# demo.net
KiCad netlist of a schematic drawn in EAGLE
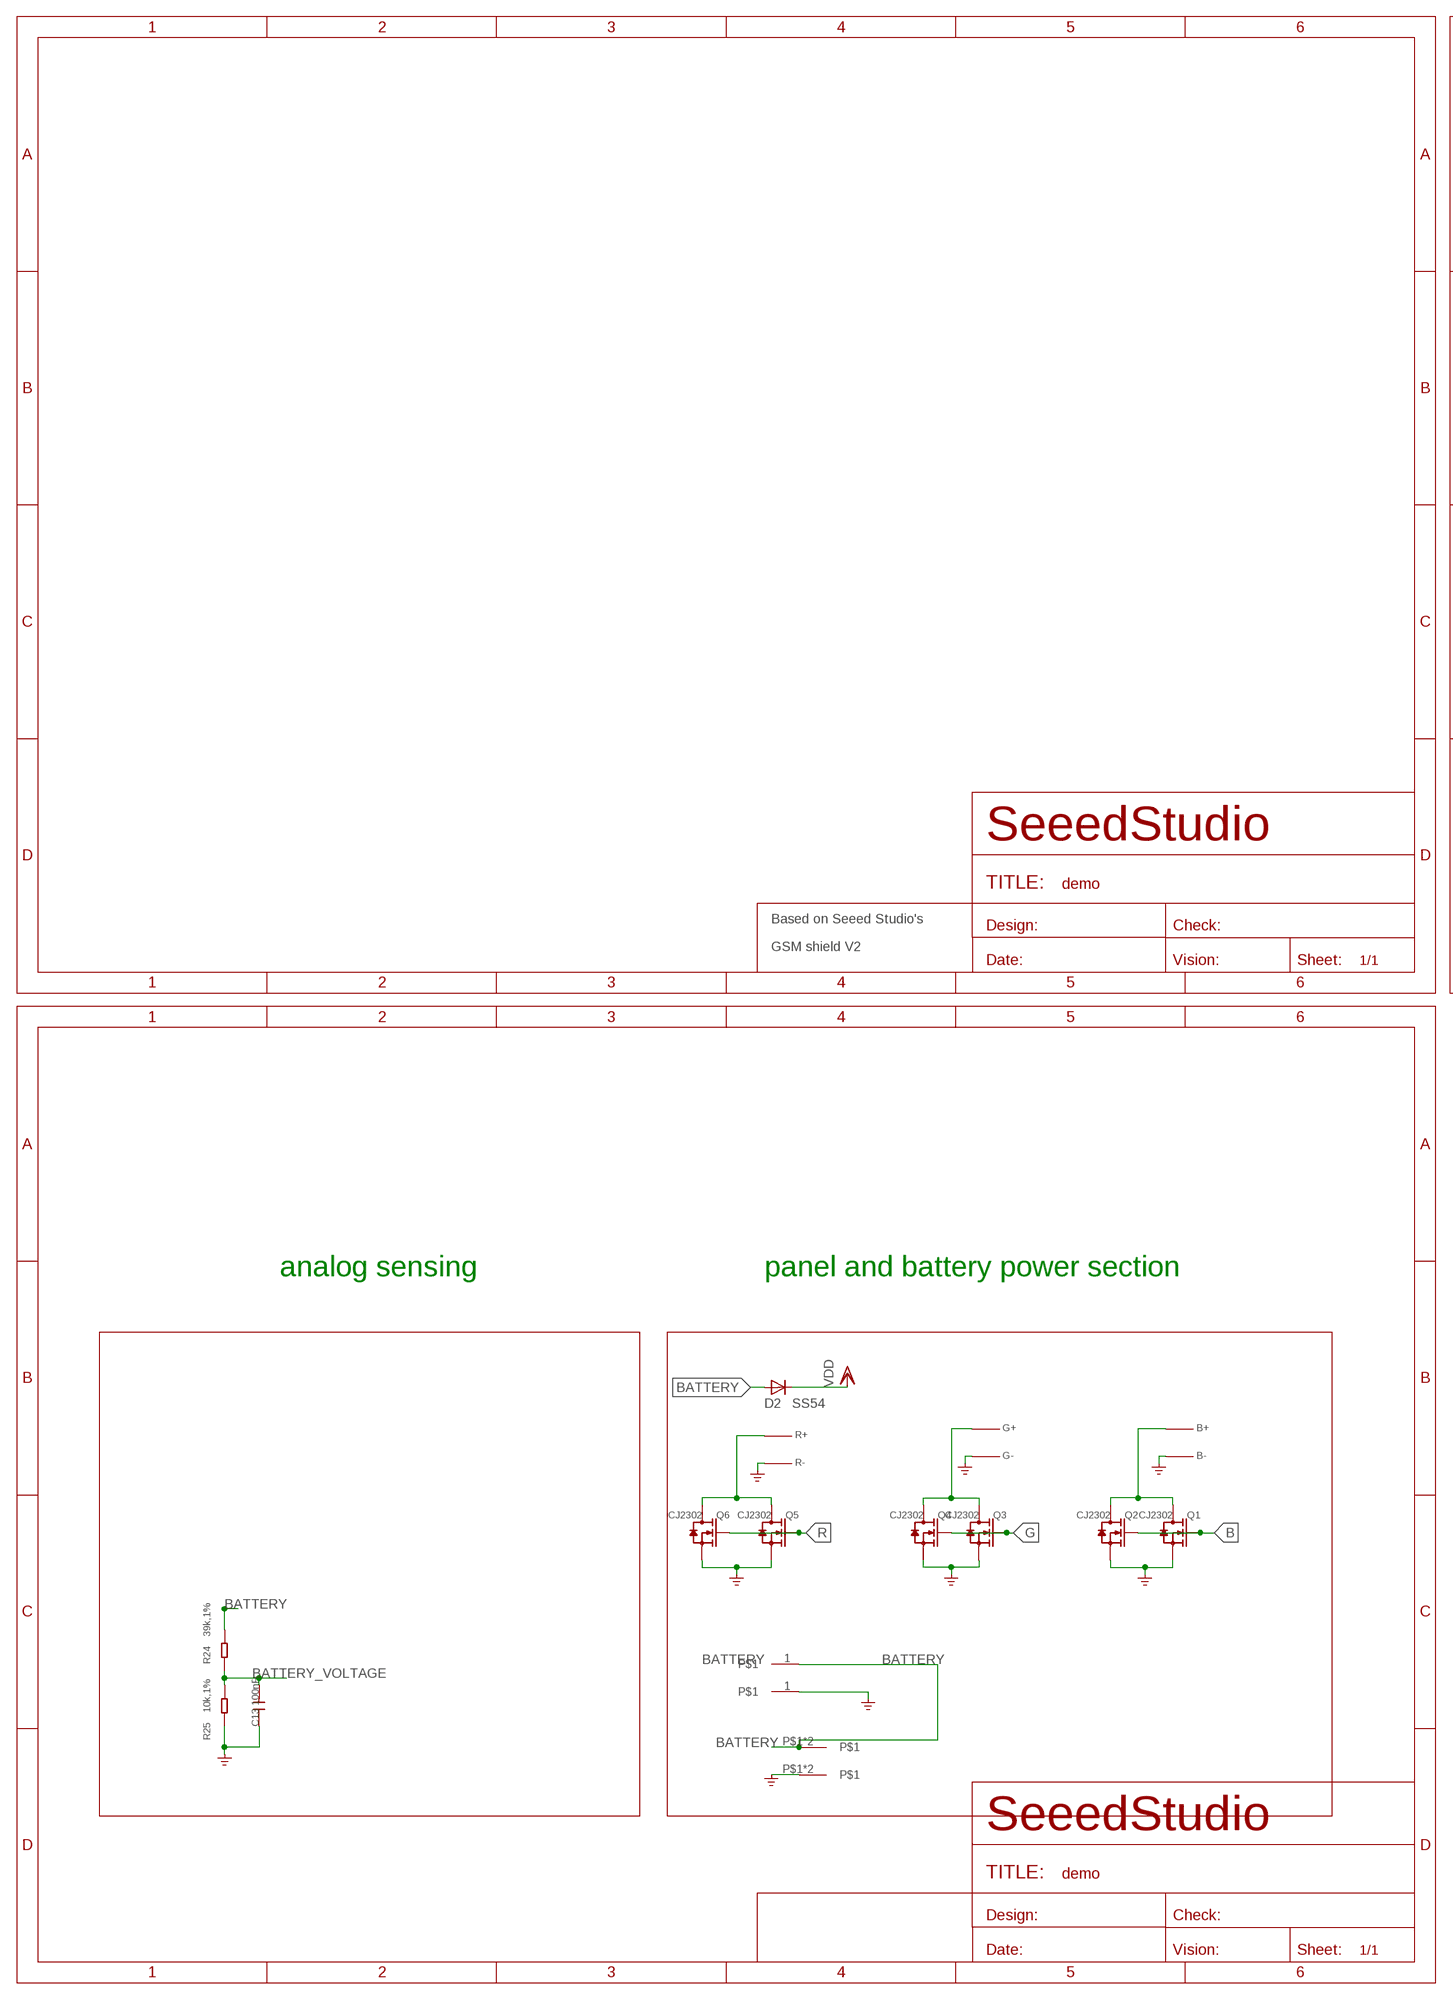
[diagram p0: schematic, sheet 1, part 1 of 2]
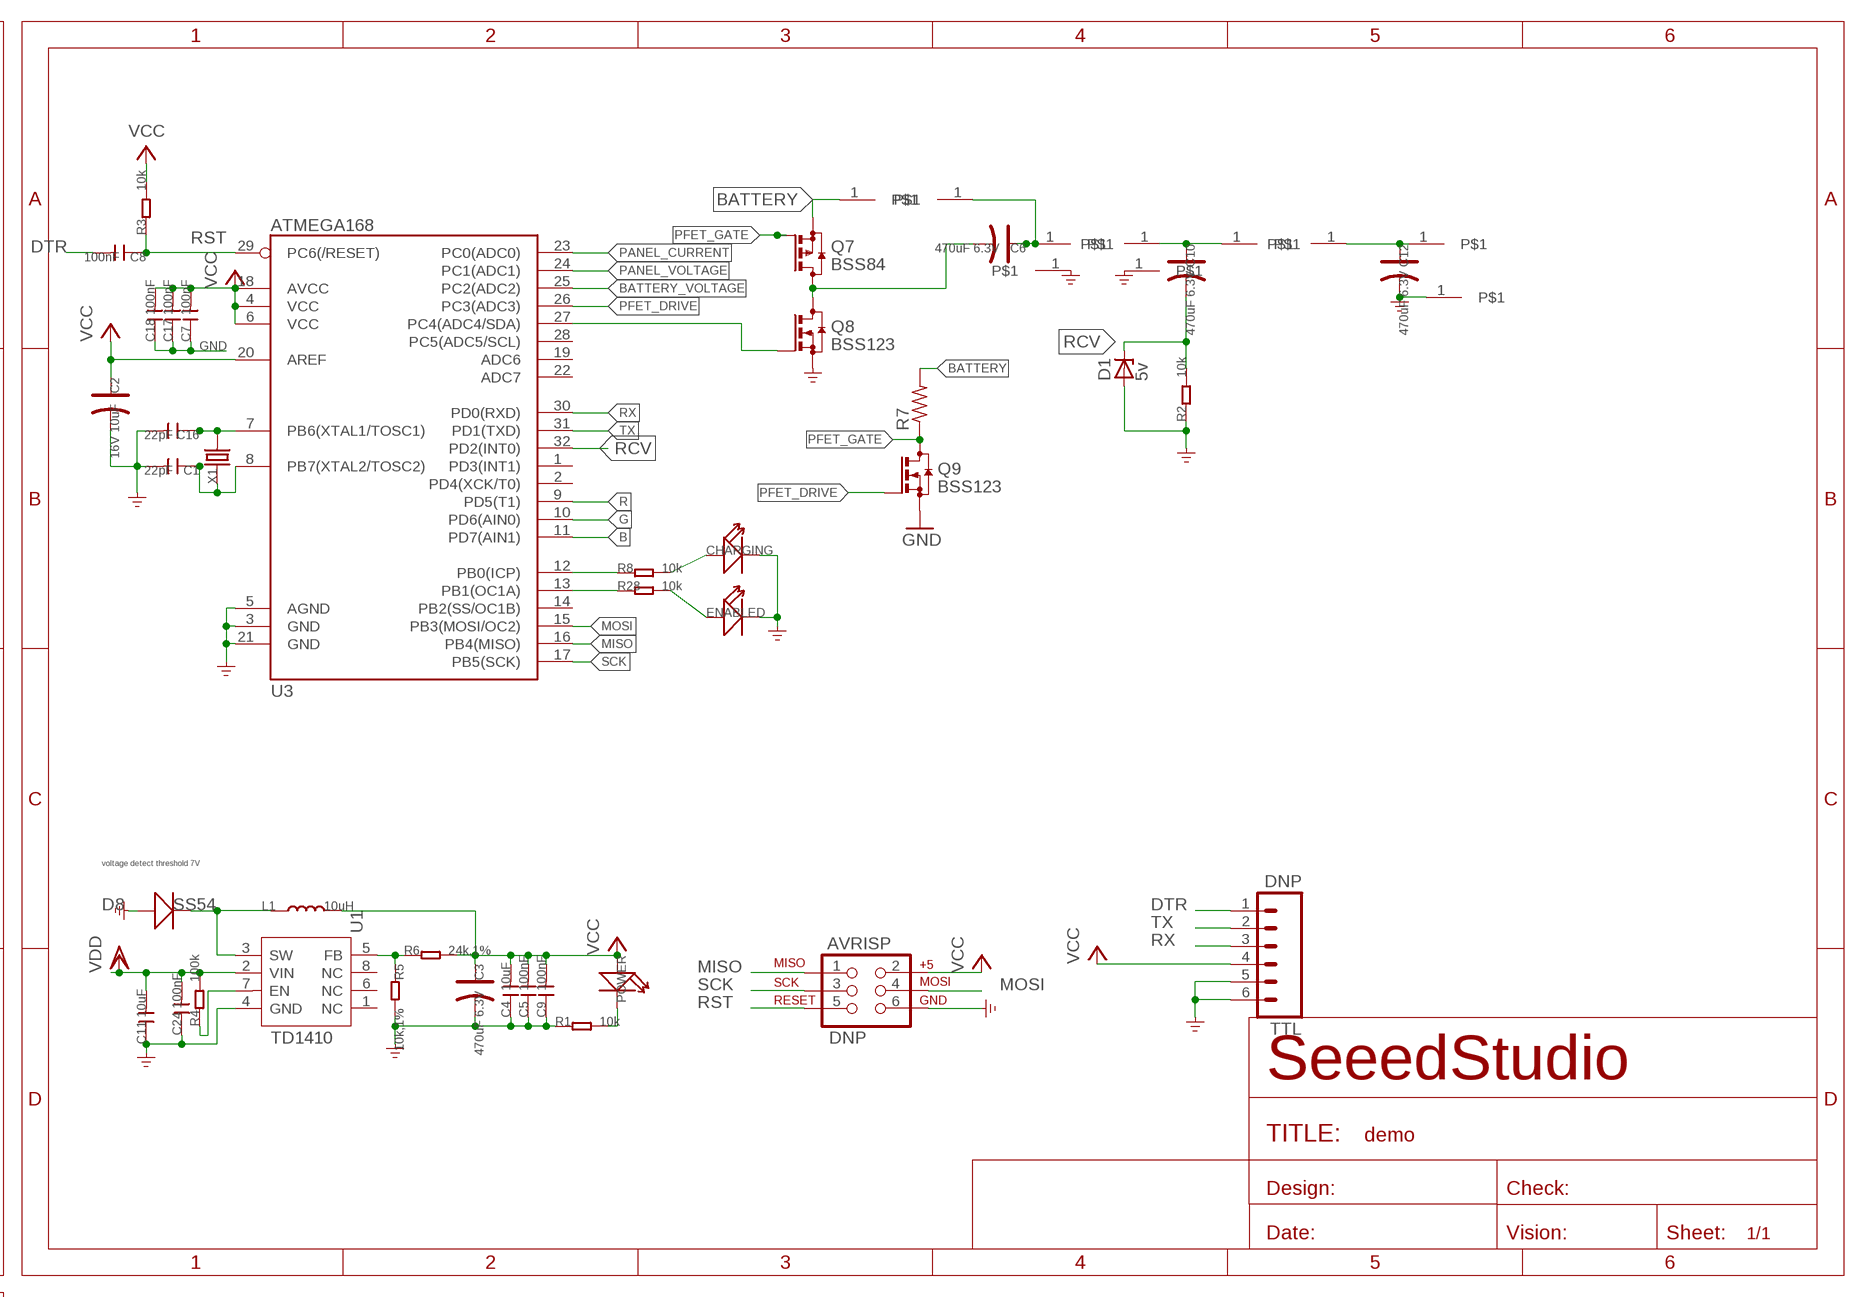
[diagram p1: schematic, sheet 1, part 2 of 2]

(export (version "E")
  (design (tool "Eeschema 10.0.6"))
  (components
    (comp (ref "AVRISP")
      (value "DNP")
      (footprint "eagle-import:2X3_LOCK")
      (libsource (lib "eagle-import") (part "AVR_SPI_PRG_62X3_LOCK"))
    )
    (comp (ref "B+")
      (value "TINYPIPES_BATTSBATT")
      (footprint "eagle-import:TINYPIPES_SBATT")
      (libsource (lib "eagle-import") (part "TINYPIPES_BATTSBATT"))
    )
    (comp (ref "B-")
      (value "TINYPIPES_BATTSBATT")
      (footprint "eagle-import:TINYPIPES_SBATT")
      (libsource (lib "eagle-import") (part "TINYPIPES_BATTSBATT"))
    )
    (comp (ref "BATTERY+")
      (value "TINYPIPES_BATTBATT")
      (footprint "eagle-import:TINYPIPES_BATT")
      (libsource (lib "eagle-import") (part "tinyPipes_v2.5_TINYPIPES_BATTBATT"))
    )
    (comp (ref "BATTERY-")
      (value "TINYPIPES_BATTBATT")
      (footprint "eagle-import:TINYPIPES_BATT")
      (libsource (lib "eagle-import") (part "tinyPipes_v2.5_TINYPIPES_BATTBATT"))
    )
    (comp (ref "C1")
      (value "22pF")
      (footprint "eagle-import:C0603")
      (libsource (lib "eagle-import") (part "C-0603"))
    )
    (comp (ref "C2")
      (value "16V 10uF")
      (footprint "eagle-import:AVX-A")
      (libsource (lib "eagle-import") (part "CAP-AVX-A"))
    )
    (comp (ref "C3")
      (value "470uF 6.3V")
      (footprint "eagle-import:AVX-D")
      (libsource (lib "eagle-import") (part "CAP-AVX-D"))
    )
    (comp (ref "C4")
      (value "10uF")
      (footprint "eagle-import:C0805")
      (libsource (lib "eagle-import") (part "C-0805"))
    )
    (comp (ref "C5")
      (value "100nF")
      (footprint "eagle-import:C0603")
      (libsource (lib "eagle-import") (part "C-0603"))
    )
    (comp (ref "C6")
      (value "470uF 6.3V")
      (footprint "eagle-import:AVX-D")
      (libsource (lib "eagle-import") (part "CAP-AVX-D"))
    )
    (comp (ref "C7")
      (value "100nF")
      (footprint "eagle-import:C0603")
      (libsource (lib "eagle-import") (part "C-0603"))
    )
    (comp (ref "C8")
      (value "100nF")
      (footprint "eagle-import:C0603")
      (libsource (lib "eagle-import") (part "C-0603"))
    )
    (comp (ref "C9")
      (value "100nF")
      (footprint "eagle-import:C0603")
      (libsource (lib "eagle-import") (part "C-0603"))
    )
    (comp (ref "C10")
      (value "470uF 6.3V")
      (footprint "eagle-import:AVX-D")
      (libsource (lib "eagle-import") (part "CAP-AVX-D"))
    )
    (comp (ref "C11")
      (value "10uF")
      (footprint "eagle-import:C0805")
      (libsource (lib "eagle-import") (part "C-0805"))
    )
    (comp (ref "C12")
      (value "470uF 6.3V")
      (footprint "eagle-import:AVX-D")
      (libsource (lib "eagle-import") (part "CAP-AVX-D"))
    )
    (comp (ref "C13")
      (value "100nF")
      (footprint "eagle-import:C0603")
      (libsource (lib "eagle-import") (part "C-0603"))
    )
    (comp (ref "C16")
      (value "22pF")
      (footprint "eagle-import:C0603")
      (libsource (lib "eagle-import") (part "C-0603"))
    )
    (comp (ref "C17")
      (value "100nF")
      (footprint "eagle-import:C0603")
      (libsource (lib "eagle-import") (part "C-0603"))
    )
    (comp (ref "C18")
      (value "100nF")
      (footprint "eagle-import:C0603")
      (libsource (lib "eagle-import") (part "C-0603"))
    )
    (comp (ref "C24")
      (value "100nF")
      (footprint "eagle-import:C0603")
      (libsource (lib "eagle-import") (part "C-0603"))
    )
    (comp (ref "CHARGING")
      (value "LED'0603'")
      (footprint "eagle-import:LED-0603")
      (libsource (lib "eagle-import") (part "LED'0603'"))
    )
    (comp (ref "D1")
      (value "5v")
      (footprint "eagle-import:SOD80C")
      (libsource (lib "eagle-import") (part "ZENER-DIODESOD80C"))
    )
    (comp (ref "D2")
      (value "SS54")
      (footprint "eagle-import:SMB")
      (libsource (lib "eagle-import") (part "DIODE-SMB"))
    )
    (comp (ref "D8")
      (value "SS54")
      (footprint "eagle-import:SMB")
      (libsource (lib "eagle-import") (part "D'MBRS240LT3'"))
    )
    (comp (ref "ENABLED")
      (value "LED'0603'")
      (footprint "eagle-import:LED-0603")
      (libsource (lib "eagle-import") (part "LED'0603'"))
    )
    (comp (ref "G+")
      (value "TINYPIPES_BATTSBATT")
      (footprint "eagle-import:TINYPIPES_SBATT")
      (libsource (lib "eagle-import") (part "TINYPIPES_BATTSBATT"))
    )
    (comp (ref "G-")
      (value "TINYPIPES_BATTSBATT")
      (footprint "eagle-import:TINYPIPES_SBATT")
      (libsource (lib "eagle-import") (part "TINYPIPES_BATTSBATT"))
    )
    (comp (ref "IN+")
      (value "TINYPIPES_BATTBATT")
      (footprint "eagle-import:TINYPIPES_BATT")
      (libsource (lib "eagle-import") (part "tinyPipes_v2.5_TINYPIPES_BATTBATT"))
    )
    (comp (ref "IN-")
      (value "TINYPIPES_BATTBATT")
      (footprint "eagle-import:TINYPIPES_BATT")
      (libsource (lib "eagle-import") (part "tinyPipes_v2.5_TINYPIPES_BATTBATT"))
    )
    (comp (ref "L1")
      (value "10uH")
      (footprint "eagle-import:L0630")
      (libsource (lib "eagle-import") (part "L'0630'"))
    )
    (comp (ref "L1+")
      (value "TINYPIPES_BATTBATT")
      (footprint "eagle-import:TINYPIPES_BATT")
      (libsource (lib "eagle-import") (part "tinyPipes_v2.5_TINYPIPES_BATTBATT"))
    )
    (comp (ref "L1-")
      (value "TINYPIPES_BATTBATT")
      (footprint "eagle-import:TINYPIPES_BATT")
      (libsource (lib "eagle-import") (part "tinyPipes_v2.5_TINYPIPES_BATTBATT"))
    )
    (comp (ref "L2+")
      (value "TINYPIPES_BATTBATT")
      (footprint "eagle-import:TINYPIPES_BATT")
      (libsource (lib "eagle-import") (part "tinyPipes_v2.5_TINYPIPES_BATTBATT"))
    )
    (comp (ref "L2-")
      (value "TINYPIPES_BATTBATT")
      (footprint "eagle-import:TINYPIPES_BATT")
      (libsource (lib "eagle-import") (part "tinyPipes_v2.5_TINYPIPES_BATTBATT"))
    )
    (comp (ref "LOAD+")
      (value "TINYPIPES_BATTBATT")
      (footprint "eagle-import:TINYPIPES_BATT")
      (libsource (lib "eagle-import") (part "tinyPipes_v2.5_TINYPIPES_BATTBATT"))
    )
    (comp (ref "LOAD-")
      (value "TINYPIPES_BATTBATT")
      (footprint "eagle-import:TINYPIPES_BATT")
      (libsource (lib "eagle-import") (part "tinyPipes_v2.5_TINYPIPES_BATTBATT"))
    )
    (comp (ref "OUT+")
      (value "TINYPIPES_BATTBATT")
      (footprint "eagle-import:TINYPIPES_BATT")
      (libsource (lib "eagle-import") (part "tinyPipes_v2.5_TINYPIPES_BATTBATT"))
    )
    (comp (ref "OUT-")
      (value "TINYPIPES_BATTBATT")
      (footprint "eagle-import:TINYPIPES_BATT")
      (libsource (lib "eagle-import") (part "tinyPipes_v2.5_TINYPIPES_BATTBATT"))
    )
    (comp (ref "PANEL+")
      (value "TINYPIPES_BATTPANEL")
      (footprint "eagle-import:TINYPIPES_PANEL")
      (libsource (lib "eagle-import") (part "tinyPipes_v2.5_TINYPIPES_BATTPANEL"))
    )
    (comp (ref "PANEL-")
      (value "TINYPIPES_BATTPANEL")
      (footprint "eagle-import:TINYPIPES_PANEL")
      (libsource (lib "eagle-import") (part "tinyPipes_v2.5_TINYPIPES_BATTPANEL"))
    )
    (comp (ref "POWER")
      (value "LED'0603'")
      (footprint "eagle-import:LED-0603")
      (libsource (lib "eagle-import") (part "LED'0603'"))
    )
    (comp (ref "Q1")
      (value "CJ2302")
      (footprint "eagle-import:SOT23")
      (libsource (lib "eagle-import") (part "MOSFET-N'SOT23'"))
    )
    (comp (ref "Q2")
      (value "CJ2302")
      (footprint "eagle-import:SOT23")
      (libsource (lib "eagle-import") (part "MOSFET-N'SOT23'"))
    )
    (comp (ref "Q3")
      (value "CJ2302")
      (footprint "eagle-import:SOT23")
      (libsource (lib "eagle-import") (part "MOSFET-N'SOT23'"))
    )
    (comp (ref "Q4")
      (value "CJ2302")
      (footprint "eagle-import:SOT23")
      (libsource (lib "eagle-import") (part "MOSFET-N'SOT23'"))
    )
    (comp (ref "Q5")
      (value "CJ2302")
      (footprint "eagle-import:SOT23")
      (libsource (lib "eagle-import") (part "MOSFET-N'SOT23'"))
    )
    (comp (ref "Q6")
      (value "CJ2302")
      (footprint "eagle-import:SOT23")
      (libsource (lib "eagle-import") (part "MOSFET-N'SOT23'"))
    )
    (comp (ref "Q7")
      (value "BSS84")
      (footprint "eagle-import:SOT23")
      (libsource (lib "eagle-import") (part "BSS84"))
    )
    (comp (ref "Q8")
      (value "BSS123")
      (footprint "eagle-import:SOT23")
      (libsource (lib "eagle-import") (part "BSS123"))
    )
    (comp (ref "Q9")
      (value "BSS123")
      (footprint "eagle-import:SOT23")
      (libsource (lib "eagle-import") (part "BSS123"))
    )
    (comp (ref "R+")
      (value "TINYPIPES_BATTSBATT")
      (footprint "eagle-import:TINYPIPES_SBATT")
      (libsource (lib "eagle-import") (part "TINYPIPES_BATTSBATT"))
    )
    (comp (ref "R-")
      (value "TINYPIPES_BATTSBATT")
      (footprint "eagle-import:TINYPIPES_SBATT")
      (libsource (lib "eagle-import") (part "TINYPIPES_BATTSBATT"))
    )
    (comp (ref "R1")
      (value "10k")
      (footprint "eagle-import:R0603")
      (libsource (lib "eagle-import") (part "R-0603"))
    )
    (comp (ref "R2")
      (value "10k")
      (footprint "eagle-import:R0603")
      (libsource (lib "eagle-import") (part "R-0603"))
    )
    (comp (ref "R3")
      (value "10k")
      (footprint "eagle-import:R0603")
      (libsource (lib "eagle-import") (part "R-0603"))
    )
    (comp (ref "R4")
      (value "100k")
      (footprint "eagle-import:R0603")
      (libsource (lib "eagle-import") (part "R-0603"))
    )
    (comp (ref "R5")
      (value "10k,1%")
      (footprint "eagle-import:R0603")
      (libsource (lib "eagle-import") (part "R-0603"))
    )
    (comp (ref "R6")
      (value "24k,1%")
      (footprint "eagle-import:R0603")
      (libsource (lib "eagle-import") (part "R-0603"))
    )
    (comp (ref "R7")
      (value "R-US_R0603")
      (footprint "eagle-import:R0603")
      (libsource (lib "eagle-import") (part "R-US_R0603"))
    )
    (comp (ref "R8")
      (value "10k")
      (footprint "eagle-import:R0603")
      (libsource (lib "eagle-import") (part "R-0603"))
    )
    (comp (ref "R24")
      (value "39k,1%")
      (footprint "eagle-import:R0603")
      (libsource (lib "eagle-import") (part "R-0603"))
    )
    (comp (ref "R25")
      (value "10k,1%")
      (footprint "eagle-import:R0603")
      (libsource (lib "eagle-import") (part "R-0603"))
    )
    (comp (ref "R28")
      (value "10k")
      (footprint "eagle-import:R0603")
      (libsource (lib "eagle-import") (part "R-0603"))
    )
    (comp (ref "TTL")
      (value "DNP")
      (footprint "eagle-import:1X06_LOCK")
      (libsource (lib "eagle-import") (part "M06LOCK"))
    )
    (comp (ref "U1")
      (value "TD1410")
      (footprint "eagle-import:SOP8")
      (libsource (lib "eagle-import") (part "TD1410"))
    )
    (comp (ref "U3")
      (value "ATMEGA168")
      (footprint "eagle-import:TQFP32-08")
      (libsource (lib "eagle-import") (part "ATMEGA168"))
    )
    (comp (ref "X1")
      (value "CRYSTAL'5032'")
      (footprint "eagle-import:2P-SMD-5X3.2")
      (libsource (lib "eagle-import") (part "CRYSTAL'5032'"))
    )
  )
  (nets
    (net (code "1") (name "/DTR") (class "Default")
      (node (ref "C8") (pin "2") (pinfunction "2_2") (pintype "passive"))
      (node (ref "TTL") (pin "1") (pinfunction "1_1") (pintype "passive"))
    )
    (net (code "2") (name "/RST") (class "Default")
      (node (ref "AVRISP") (pin "5") (pinfunction "5_5") (pintype "passive"))
      (node (ref "C8") (pin "1") (pinfunction "1_1") (pintype "passive"))
      (node (ref "R3") (pin "1") (pinfunction "1_1") (pintype "passive"))
      (node (ref "U3") (pin "29") (pinfunction "PC6(/RESET)_29") (pintype "bidirectional"))
    )
    (net (code "3") (name "B") (class "Default")
      (node (ref "Q1") (pin "1") (pinfunction "G_1") (pintype "passive"))
      (node (ref "Q2") (pin "1") (pinfunction "G_1") (pintype "passive"))
      (node (ref "U3") (pin "11") (pinfunction "PD7(AIN1)_11") (pintype "bidirectional"))
    )
    (net (code "4") (name "BATTERY") (class "Default")
      (node (ref "BATTERY+") (pin "1") (pinfunction "P$1_1") (pintype "bidirectional"))
      (node (ref "D2") (pin "A") (pinfunction "A_A") (pintype "passive"))
      (node (ref "L1+") (pin "1") (pinfunction "P$1_1") (pintype "bidirectional"))
      (node (ref "PANEL+") (pin "P$1") (pinfunction "P$1_P$1") (pintype "bidirectional"))
      (node (ref "PANEL+") (pin "P$2") (pinfunction "P$1_P$2") (pintype "bidirectional"))
      (node (ref "Q7") (pin "2") (pinfunction "S_2") (pintype "passive"))
      (node (ref "R24") (pin "2") (pinfunction "2_2") (pintype "passive"))
      (node (ref "R7") (pin "2") (pinfunction "2_2") (pintype "passive"))
    )
    (net (code "5") (name "BATTERY_VOLTAGE") (class "Default")
      (node (ref "C13") (pin "2") (pinfunction "2_2") (pintype "passive"))
      (node (ref "R24") (pin "1") (pinfunction "1_1") (pintype "passive"))
      (node (ref "R25") (pin "2") (pinfunction "2_2") (pintype "passive"))
      (node (ref "U3") (pin "25") (pinfunction "PC2(ADC2)_25") (pintype "bidirectional"))
    )
    (net (code "6") (name "G") (class "Default")
      (node (ref "Q3") (pin "1") (pinfunction "G_1") (pintype "passive"))
      (node (ref "Q4") (pin "1") (pinfunction "G_1") (pintype "passive"))
      (node (ref "U3") (pin "10") (pinfunction "PD6(AIN0)_10") (pintype "bidirectional"))
    )
    (net (code "7") (name "GND") (class "Default")
      (node (ref "AVRISP") (pin "6") (pinfunction "6_6") (pintype "passive"))
      (node (ref "B-") (pin "P$1") (pinfunction "P$1_P$1") (pintype "bidirectional"))
      (node (ref "BATTERY-") (pin "1") (pinfunction "P$1_1") (pintype "bidirectional"))
      (node (ref "C1") (pin "2") (pinfunction "2_2") (pintype "passive"))
      (node (ref "C11") (pin "1") (pinfunction "1_1") (pintype "passive"))
      (node (ref "C12") (pin "-") (pinfunction "-_-") (pintype "passive"))
      (node (ref "C13") (pin "1") (pinfunction "1_1") (pintype "passive"))
      (node (ref "C16") (pin "2") (pinfunction "2_2") (pintype "passive"))
      (node (ref "C17") (pin "1") (pinfunction "1_1") (pintype "passive"))
      (node (ref "C18") (pin "1") (pinfunction "1_1") (pintype "passive"))
      (node (ref "C2") (pin "-") (pinfunction "-_-") (pintype "passive"))
      (node (ref "C24") (pin "1") (pinfunction "1_1") (pintype "passive"))
      (node (ref "C3") (pin "-") (pinfunction "-_-") (pintype "passive"))
      (node (ref "C4") (pin "1") (pinfunction "1_1") (pintype "passive"))
      (node (ref "C5") (pin "1") (pinfunction "1_1") (pintype "passive"))
      (node (ref "C7") (pin "1") (pinfunction "1_1") (pintype "passive"))
      (node (ref "C9") (pin "1") (pinfunction "1_1") (pintype "passive"))
      (node (ref "CHARGING") (pin "-") (pinfunction "-_-") (pintype "passive"))
      (node (ref "D1") (pin "A") (pinfunction "A_A") (pintype "passive"))
      (node (ref "D8") (pin "+") (pinfunction "+_+") (pintype "passive"))
      (node (ref "ENABLED") (pin "-") (pinfunction "-_-") (pintype "passive"))
      (node (ref "G-") (pin "P$1") (pinfunction "P$1_P$1") (pintype "bidirectional"))
      (node (ref "IN-") (pin "1") (pinfunction "P$1_1") (pintype "bidirectional"))
      (node (ref "LOAD-") (pin "1") (pinfunction "P$1_1") (pintype "bidirectional"))
      (node (ref "OUT-") (pin "1") (pinfunction "P$1_1") (pintype "bidirectional"))
      (node (ref "PANEL-") (pin "P$1") (pinfunction "P$1_P$1") (pintype "bidirectional"))
      (node (ref "PANEL-") (pin "P$2") (pinfunction "P$1_P$2") (pintype "bidirectional"))
      (node (ref "Q1") (pin "2") (pinfunction "S_2") (pintype "passive"))
      (node (ref "Q2") (pin "2") (pinfunction "S_2") (pintype "passive"))
      (node (ref "Q3") (pin "2") (pinfunction "S_2") (pintype "passive"))
      (node (ref "Q4") (pin "2") (pinfunction "S_2") (pintype "passive"))
      (node (ref "Q5") (pin "2") (pinfunction "S_2") (pintype "passive"))
      (node (ref "Q6") (pin "2") (pinfunction "S_2") (pintype "passive"))
      (node (ref "Q8") (pin "2") (pinfunction "S_2") (pintype "passive"))
      (node (ref "Q9") (pin "2") (pinfunction "S_2") (pintype "passive"))
      (node (ref "R-") (pin "P$1") (pinfunction "P$1_P$1") (pintype "bidirectional"))
      (node (ref "R1") (pin "1") (pinfunction "1_1") (pintype "passive"))
      (node (ref "R2") (pin "1") (pinfunction "1_1") (pintype "passive"))
      (node (ref "R25") (pin "1") (pinfunction "1_1") (pintype "passive"))
      (node (ref "R5") (pin "2") (pinfunction "2_2") (pintype "passive"))
      (node (ref "TTL") (pin "5") (pinfunction "5_5") (pintype "passive"))
      (node (ref "TTL") (pin "6") (pinfunction "6_6") (pintype "passive"))
      (node (ref "U1") (pin "4") (pinfunction "GND_4") (pintype "power_in"))
      (node (ref "U3") (pin "21") (pinfunction "GND_21") (pintype "bidirectional"))
      (node (ref "U3") (pin "3") (pinfunction "GND_3") (pintype "bidirectional"))
      (node (ref "U3") (pin "5") (pinfunction "AGND_5") (pintype "bidirectional"))
    )
    (net (code "8") (name "MISO") (class "Default")
      (node (ref "AVRISP") (pin "1") (pinfunction "1_1") (pintype "passive"))
      (node (ref "U3") (pin "16") (pinfunction "PB4(MISO)_16") (pintype "bidirectional"))
    )
    (net (code "9") (name "MOSI") (class "Default")
      (node (ref "AVRISP") (pin "4") (pinfunction "4_4") (pintype "passive"))
      (node (ref "U3") (pin "15") (pinfunction "PB3(MOSI/OC2)_15") (pintype "bidirectional"))
    )
    (net (code "10") (name "Net-(CHARGING-Pad+)") (class "Default")
      (node (ref "CHARGING") (pin "+") (pinfunction "+_+") (pintype "passive"))
      (node (ref "R8") (pin "2") (pinfunction "2_2") (pintype "passive"))
    )
    (net (code "11") (name "Net-(ENABLED-Pad+)") (class "Default")
      (node (ref "ENABLED") (pin "+") (pinfunction "+_+") (pintype "passive"))
      (node (ref "R28") (pin "2") (pinfunction "2_2") (pintype "passive"))
    )
    (net (code "12") (name "Net-(IN+-P$1)") (class "Default")
      (node (ref "C10") (pin "+") (pinfunction "+_+") (pintype "passive"))
      (node (ref "IN+") (pin "1") (pinfunction "P$1_1") (pintype "bidirectional"))
      (node (ref "L2+") (pin "1") (pinfunction "P$1_1") (pintype "bidirectional"))
    )
    (net (code "13") (name "Net-(L1--P$1)") (class "Default")
      (node (ref "C6") (pin "+") (pinfunction "+_+") (pintype "passive"))
      (node (ref "L1-") (pin "1") (pinfunction "P$1_1") (pintype "bidirectional"))
      (node (ref "OUT+") (pin "1") (pinfunction "P$1_1") (pintype "bidirectional"))
    )
    (net (code "14") (name "Net-(L2--P$1)") (class "Default")
      (node (ref "C12") (pin "+") (pinfunction "+_+") (pintype "passive"))
      (node (ref "L2-") (pin "1") (pinfunction "P$1_1") (pintype "bidirectional"))
      (node (ref "LOAD+") (pin "1") (pinfunction "P$1_1") (pintype "bidirectional"))
    )
    (net (code "15") (name "Net-(POWER-Pad-)") (class "Default")
      (node (ref "POWER") (pin "-") (pinfunction "-_-") (pintype "passive"))
      (node (ref "R1") (pin "2") (pinfunction "2_2") (pintype "passive"))
    )
    (net (code "16") (name "Net-(Q1-D)") (class "Default")
      (node (ref "B+") (pin "P$1") (pinfunction "P$1_P$1") (pintype "bidirectional"))
      (node (ref "Q1") (pin "3") (pinfunction "D_3") (pintype "passive"))
      (node (ref "Q2") (pin "3") (pinfunction "D_3") (pintype "passive"))
    )
    (net (code "17") (name "Net-(Q3-D)") (class "Default")
      (node (ref "G+") (pin "P$1") (pinfunction "P$1_P$1") (pintype "bidirectional"))
      (node (ref "Q3") (pin "3") (pinfunction "D_3") (pintype "passive"))
      (node (ref "Q4") (pin "3") (pinfunction "D_3") (pintype "passive"))
    )
    (net (code "18") (name "Net-(Q5-D)") (class "Default")
      (node (ref "Q5") (pin "3") (pinfunction "D_3") (pintype "passive"))
      (node (ref "Q6") (pin "3") (pinfunction "D_3") (pintype "passive"))
      (node (ref "R+") (pin "P$1") (pinfunction "P$1_P$1") (pintype "bidirectional"))
    )
    (net (code "19") (name "Net-(Q7-D)") (class "Default")
      (node (ref "C6") (pin "-") (pinfunction "-_-") (pintype "passive"))
      (node (ref "Q7") (pin "3") (pinfunction "D_3") (pintype "passive"))
      (node (ref "Q8") (pin "3") (pinfunction "D_3") (pintype "passive"))
    )
    (net (code "20") (name "Net-(Q8-G)") (class "Default")
      (node (ref "Q8") (pin "1") (pinfunction "G_1") (pintype "passive"))
      (node (ref "U3") (pin "27") (pinfunction "PC4(ADC4/SDA)_27") (pintype "bidirectional"))
    )
    (net (code "21") (name "Net-(U1-EN)") (class "Default")
      (node (ref "R4") (pin "1") (pinfunction "1_1") (pintype "passive"))
      (node (ref "U1") (pin "7") (pinfunction "EN_7") (pintype "input"))
    )
    (net (code "22") (name "Net-(U1-FB)") (class "Default")
      (node (ref "R5") (pin "1") (pinfunction "1_1") (pintype "passive"))
      (node (ref "R6") (pin "1") (pinfunction "1_1") (pintype "passive"))
      (node (ref "U1") (pin "5") (pinfunction "FB_5") (pintype "input"))
    )
    (net (code "23") (name "Net-(U1-SW)") (class "Default")
      (node (ref "D8") (pin "-") (pinfunction "-_-") (pintype "passive"))
      (node (ref "L1") (pin "1") (pinfunction "1_1") (pintype "passive"))
      (node (ref "U1") (pin "3") (pinfunction "SW_3") (pintype "output"))
    )
    (net (code "24") (name "Net-(U3-PB0(ICP))") (class "Default")
      (node (ref "R8") (pin "1") (pinfunction "1_1") (pintype "passive"))
      (node (ref "U3") (pin "12") (pinfunction "PB0(ICP)_12") (pintype "bidirectional"))
    )
    (net (code "25") (name "Net-(U3-PB1(OC1A))") (class "Default")
      (node (ref "R28") (pin "1") (pinfunction "1_1") (pintype "passive"))
      (node (ref "U3") (pin "13") (pinfunction "PB1(OC1A)_13") (pintype "bidirectional"))
    )
    (net (code "26") (name "Net-(U3-PB6(XTAL1{slash}TOSC1))") (class "Default")
      (node (ref "C16") (pin "1") (pinfunction "1_1") (pintype "passive"))
      (node (ref "U3") (pin "7") (pinfunction "PB6(XTAL1/TOSC1)_7") (pintype "bidirectional"))
      (node (ref "X1") (pin "2") (pinfunction "2_2") (pintype "passive"))
    )
    (net (code "27") (name "Net-(U3-PB7(XTAL2{slash}TOSC2))") (class "Default")
      (node (ref "C1") (pin "1") (pinfunction "1_1") (pintype "passive"))
      (node (ref "U3") (pin "8") (pinfunction "PB7(XTAL2/TOSC2)_8") (pintype "bidirectional"))
      (node (ref "X1") (pin "1") (pinfunction "1_1") (pintype "passive"))
    )
    (net (code "28") (name "PANEL_CURRENT") (class "Default")
      (node (ref "U3") (pin "23") (pinfunction "PC0(ADC0)_23") (pintype "bidirectional"))
    )
    (net (code "29") (name "PANEL_VOLTAGE") (class "Default")
      (node (ref "U3") (pin "24") (pinfunction "PC1(ADC1)_24") (pintype "bidirectional"))
    )
    (net (code "30") (name "PFET_DRIVE") (class "Default")
      (node (ref "Q9") (pin "1") (pinfunction "G_1") (pintype "passive"))
      (node (ref "U3") (pin "26") (pinfunction "PC3(ADC3)_26") (pintype "bidirectional"))
    )
    (net (code "31") (name "PFET_GATE") (class "Default")
      (node (ref "Q7") (pin "1") (pinfunction "G_1") (pintype "passive"))
      (node (ref "Q9") (pin "3") (pinfunction "D_3") (pintype "passive"))
      (node (ref "R7") (pin "1") (pinfunction "1_1") (pintype "passive"))
    )
    (net (code "32") (name "R") (class "Default")
      (node (ref "Q5") (pin "1") (pinfunction "G_1") (pintype "passive"))
      (node (ref "Q6") (pin "1") (pinfunction "G_1") (pintype "passive"))
      (node (ref "U3") (pin "9") (pinfunction "PD5(T1)_9") (pintype "bidirectional"))
    )
    (net (code "33") (name "RCV") (class "Default")
      (node (ref "C10") (pin "-") (pinfunction "-_-") (pintype "passive"))
      (node (ref "D1") (pin "C") (pinfunction "C_C") (pintype "passive"))
      (node (ref "R2") (pin "2") (pinfunction "2_2") (pintype "passive"))
      (node (ref "U3") (pin "32") (pinfunction "PD2(INT0)_32") (pintype "bidirectional"))
    )
    (net (code "34") (name "RX") (class "Default")
      (node (ref "TTL") (pin "3") (pinfunction "3_3") (pintype "passive"))
      (node (ref "U3") (pin "30") (pinfunction "PD0(RXD)_30") (pintype "bidirectional"))
    )
    (net (code "35") (name "SCK") (class "Default")
      (node (ref "AVRISP") (pin "3") (pinfunction "3_3") (pintype "passive"))
      (node (ref "U3") (pin "17") (pinfunction "PB5(SCK)_17") (pintype "bidirectional"))
    )
    (net (code "36") (name "TX") (class "Default")
      (node (ref "TTL") (pin "2") (pinfunction "2_2") (pintype "passive"))
      (node (ref "U3") (pin "31") (pinfunction "PD1(TXD)_31") (pintype "bidirectional"))
    )
    (net (code "37") (name "VCC") (class "Default")
      (node (ref "AVRISP") (pin "2") (pinfunction "2_2") (pintype "passive"))
      (node (ref "C17") (pin "2") (pinfunction "2_2") (pintype "passive"))
      (node (ref "C18") (pin "2") (pinfunction "2_2") (pintype "passive"))
      (node (ref "C2") (pin "+") (pinfunction "+_+") (pintype "passive"))
      (node (ref "C3") (pin "+") (pinfunction "+_+") (pintype "passive"))
      (node (ref "C4") (pin "2") (pinfunction "2_2") (pintype "passive"))
      (node (ref "C5") (pin "2") (pinfunction "2_2") (pintype "passive"))
      (node (ref "C7") (pin "2") (pinfunction "2_2") (pintype "passive"))
      (node (ref "C9") (pin "2") (pinfunction "2_2") (pintype "passive"))
      (node (ref "L1") (pin "2") (pinfunction "2_2") (pintype "passive"))
      (node (ref "POWER") (pin "+") (pinfunction "+_+") (pintype "passive"))
      (node (ref "R3") (pin "2") (pinfunction "2_2") (pintype "passive"))
      (node (ref "R6") (pin "2") (pinfunction "2_2") (pintype "passive"))
      (node (ref "TTL") (pin "4") (pinfunction "4_4") (pintype "passive"))
      (node (ref "U3") (pin "18") (pinfunction "AVCC_18") (pintype "bidirectional"))
      (node (ref "U3") (pin "20") (pinfunction "AREF_20") (pintype "bidirectional"))
      (node (ref "U3") (pin "4") (pinfunction "VCC_4") (pintype "bidirectional"))
      (node (ref "U3") (pin "6") (pinfunction "VCC_6") (pintype "bidirectional"))
    )
    (net (code "38") (name "VDD") (class "Default")
      (node (ref "C11") (pin "2") (pinfunction "2_2") (pintype "passive"))
      (node (ref "C24") (pin "2") (pinfunction "2_2") (pintype "passive"))
      (node (ref "D2") (pin "C") (pinfunction "C_C") (pintype "passive"))
      (node (ref "R4") (pin "2") (pinfunction "2_2") (pintype "passive"))
      (node (ref "U1") (pin "2") (pinfunction "VIN_2") (pintype "input"))
    )
    (net (code "39") (name "unconnected-(U1-NC-Pad1)") (class "Default")
      (node (ref "U1") (pin "1") (pinfunction "NC_1") (pintype "no_connect"))
    )
    (net (code "40") (name "unconnected-(U1-NC-Pad6)") (class "Default")
      (node (ref "U1") (pin "6") (pinfunction "NC_6") (pintype "no_connect"))
    )
    (net (code "41") (name "unconnected-(U1-NC-Pad8)") (class "Default")
      (node (ref "U1") (pin "8") (pinfunction "NC_8") (pintype "no_connect"))
    )
    (net (code "42") (name "unconnected-(U3-ADC6-Pad19)") (class "Default")
      (node (ref "U3") (pin "19") (pinfunction "ADC6_19") (pintype "bidirectional"))
    )
    (net (code "43") (name "unconnected-(U3-ADC7-Pad22)") (class "Default")
      (node (ref "U3") (pin "22") (pinfunction "ADC7_22") (pintype "bidirectional"))
    )
    (net (code "44") (name "unconnected-(U3-PB2(SS{slash}OC1B)-Pad14)") (class "Default")
      (node (ref "U3") (pin "14") (pinfunction "PB2(SS/OC1B)_14") (pintype "bidirectional"))
    )
    (net (code "45") (name "unconnected-(U3-PC5(ADC5{slash}SCL)-Pad28)") (class "Default")
      (node (ref "U3") (pin "28") (pinfunction "PC5(ADC5/SCL)_28") (pintype "bidirectional"))
    )
    (net (code "46") (name "unconnected-(U3-PD3(INT1)-Pad1)") (class "Default")
      (node (ref "U3") (pin "1") (pinfunction "PD3(INT1)_1") (pintype "bidirectional"))
    )
    (net (code "47") (name "unconnected-(U3-PD4(XCK{slash}T0)-Pad2)") (class "Default")
      (node (ref "U3") (pin "2") (pinfunction "PD4(XCK/T0)_2") (pintype "bidirectional"))
    )
  )
)
